# TrickleCharging.net
KiCad netlist of a schematic drawn in Altium Designer
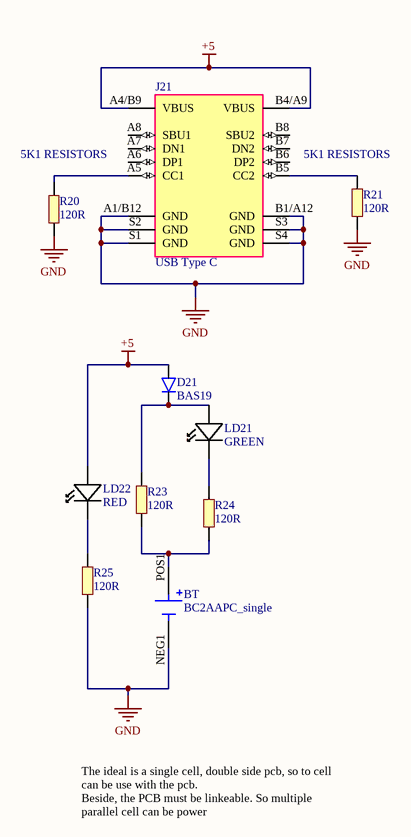
[diagram p0: TrickleCharging.SchDoc]

(export (version "E")
  (design (tool "Eeschema 10.0.6"))
  (components
    (comp (ref "BT")
      (value "BC2AAPC_single")
      (footprint "BAT_BC2AAPC_single")
      (description "BATTERY HOLDER AA 1 CELL PC PIN")
      (fields (field (name "MF") "MPD") (field (name "MP") "BC2AAPC"))
      (libsource (lib "[0801] BatteryAAholder_Single") (part "BC2AAPC_single"))
    )
    (comp (ref "D21")
      (value "BAS19")
      (footprint "SOT-23")
      (description "Diode Standard 250V 200mA Surface Mount SOT-23-3 _TO-236_")
      (fields (field (name "MF") "onsemi") (field (name "MP") "BAS19LT1G"))
      (libsource (lib "[0304]BAS19_SOT23") (part "BAS19"))
    )
    (comp (ref "J21")
      (value "USB Type C")
      (footprint "GCT_USB4110-GF-A_REVB")
      (fields (field (name "MF") "GCT") (field (name "MP") "USB4110-GF-A"))
      (libsource (lib "[0502]USB_C_2-0_SMD_RA_USB4110-GF") (part "USB4110-GF-A_REVB"))
    )
    (comp (ref "LD21")
      (value "GREEN")
      (footprint "LED 3X1.5")
      (description "Standard LED 1206")
      (libsource (lib "[0401] LEDs") (part "LED GREEN"))
    )
    (comp (ref "LD22")
      (value "RED")
      (footprint "LED 3X1.5")
      (description "Standard LED 1206")
      (libsource (lib "[0401] LEDs") (part "LED RED"))
    )
    (comp (ref "R20")
      (value "120R")
      (footprint "RESC2012X60N")
      (description "1/10W ±1% 120Ω ±100ppm/℃ 0805")
      (libsource (lib "[0001]RES0805_SMD_120R") (part "RES0805_120R"))
    )
    (comp (ref "R21")
      (value "120R")
      (footprint "RESC2012X60N")
      (description "1/10W ±1% 120Ω ±100ppm/℃ 0805")
      (libsource (lib "[0001]RES0805_SMD_120R") (part "RES0805_120R"))
    )
    (comp (ref "R23")
      (value "120R")
      (footprint "RESC2012X60N")
      (description "1/10W ±1% 120Ω ±100ppm/℃ 0805")
      (libsource (lib "[0001]RES0805_SMD_120R") (part "RES0805_120R"))
    )
    (comp (ref "R24")
      (value "120R")
      (footprint "RESC2012X60N")
      (description "1/10W ±1% 120Ω ±100ppm/℃ 0805")
      (libsource (lib "[0001]RES0805_SMD_120R") (part "RES0805_120R"))
    )
    (comp (ref "R25")
      (value "120R")
      (footprint "RESC2012X60N")
      (description "1/10W ±1% 120Ω ±100ppm/℃ 0805")
      (libsource (lib "[0001]RES0805_SMD_120R") (part "RES0805_120R"))
    )
  )
  (nets
    (net (code "1") (name "+5") (class "Default")
      (node (ref "D21") (pin "1") (pinfunction "A_1") (pintype "passive"))
      (node (ref "J21") (pin "A4/B9") (pinfunction "VBUS_A4/B9") (pintype "power_in"))
      (node (ref "J21") (pin "B4/A9") (pinfunction "VBUS_B4/A9") (pintype "power_in"))
      (node (ref "LD22") (pin "1") (pinfunction "AR_1") (pintype "passive"))
    )
    (net (code "2") (name "GND") (class "Default")
      (node (ref "BT") (pin "NEG1") (pinfunction "NEG1_NEG1") (pintype "passive"))
      (node (ref "J21") (pin "A1/B12") (pinfunction "GND_A1/B12") (pintype "power_in"))
      (node (ref "J21") (pin "B1/A12") (pinfunction "GND_B1/A12") (pintype "power_in"))
      (node (ref "J21") (pin "S1") (pinfunction "GND_S1") (pintype "power_in"))
      (node (ref "J21") (pin "S2") (pinfunction "GND_S2") (pintype "power_in"))
      (node (ref "J21") (pin "S3") (pinfunction "GND_S3") (pintype "power_in"))
      (node (ref "J21") (pin "S4") (pinfunction "GND_S4") (pintype "power_in"))
      (node (ref "R20") (pin "1") (pinfunction "1_1") (pintype "passive"))
      (node (ref "R21") (pin "1") (pinfunction "1_1") (pintype "passive"))
      (node (ref "R25") (pin "1") (pinfunction "1_1") (pintype "passive"))
    )
    (net (code "3") (name "Net-(BT-PadPOS1)") (class "Default")
      (node (ref "BT") (pin "POS1") (pinfunction "POS1_POS1") (pintype "passive"))
      (node (ref "R23") (pin "1") (pinfunction "1_1") (pintype "passive"))
      (node (ref "R24") (pin "1") (pinfunction "1_1") (pintype "passive"))
    )
    (net (code "4") (name "Net-(D21-K)") (class "Default")
      (node (ref "D21") (pin "3") (pinfunction "K_3") (pintype "passive"))
      (node (ref "LD21") (pin "1") (pinfunction "AR_1") (pintype "passive"))
      (node (ref "R23") (pin "2") (pinfunction "2_2") (pintype "passive"))
    )
    (net (code "5") (name "Net-(J21-CC1)") (class "Default")
      (node (ref "J21") (pin "A5") (pinfunction "CC1_A5") (pintype "bidirectional"))
      (node (ref "R20") (pin "2") (pinfunction "2_2") (pintype "passive"))
    )
    (net (code "6") (name "Net-(J21-CC2)") (class "Default")
      (node (ref "J21") (pin "B5") (pinfunction "CC2_B5") (pintype "bidirectional"))
      (node (ref "R21") (pin "2") (pinfunction "2_2") (pintype "passive"))
    )
    (net (code "7") (name "Net-(LD21-KR)") (class "Default")
      (node (ref "LD21") (pin "2") (pinfunction "KR_2") (pintype "passive"))
      (node (ref "R24") (pin "2") (pinfunction "2_2") (pintype "passive"))
    )
    (net (code "8") (name "Net-(LD22-KR)") (class "Default")
      (node (ref "LD22") (pin "2") (pinfunction "KR_2") (pintype "passive"))
      (node (ref "R25") (pin "2") (pinfunction "2_2") (pintype "passive"))
    )
    (net (code "9") (name "unconnected-(J21-DN1-PadA7)") (class "Default")
      (node (ref "J21") (pin "A7") (pinfunction "DN1_A7") (pintype "bidirectional"))
    )
    (net (code "10") (name "unconnected-(J21-DN2-PadB7)") (class "Default")
      (node (ref "J21") (pin "B7") (pinfunction "DN2_B7") (pintype "bidirectional"))
    )
    (net (code "11") (name "unconnected-(J21-DP1-PadA6)") (class "Default")
      (node (ref "J21") (pin "A6") (pinfunction "DP1_A6") (pintype "bidirectional"))
    )
    (net (code "12") (name "unconnected-(J21-DP2-PadB6)") (class "Default")
      (node (ref "J21") (pin "B6") (pinfunction "DP2_B6") (pintype "bidirectional"))
    )
    (net (code "13") (name "unconnected-(J21-SBU1-PadA8)") (class "Default")
      (node (ref "J21") (pin "A8") (pinfunction "SBU1_A8") (pintype "bidirectional"))
    )
    (net (code "14") (name "unconnected-(J21-SBU2-PadB8)") (class "Default")
      (node (ref "J21") (pin "B8") (pinfunction "SBU2_B8") (pintype "bidirectional"))
    )
  )
)
